# ETH_PCIE_PHY.net
KiCad netlist of a schematic drawn in Altium Designer
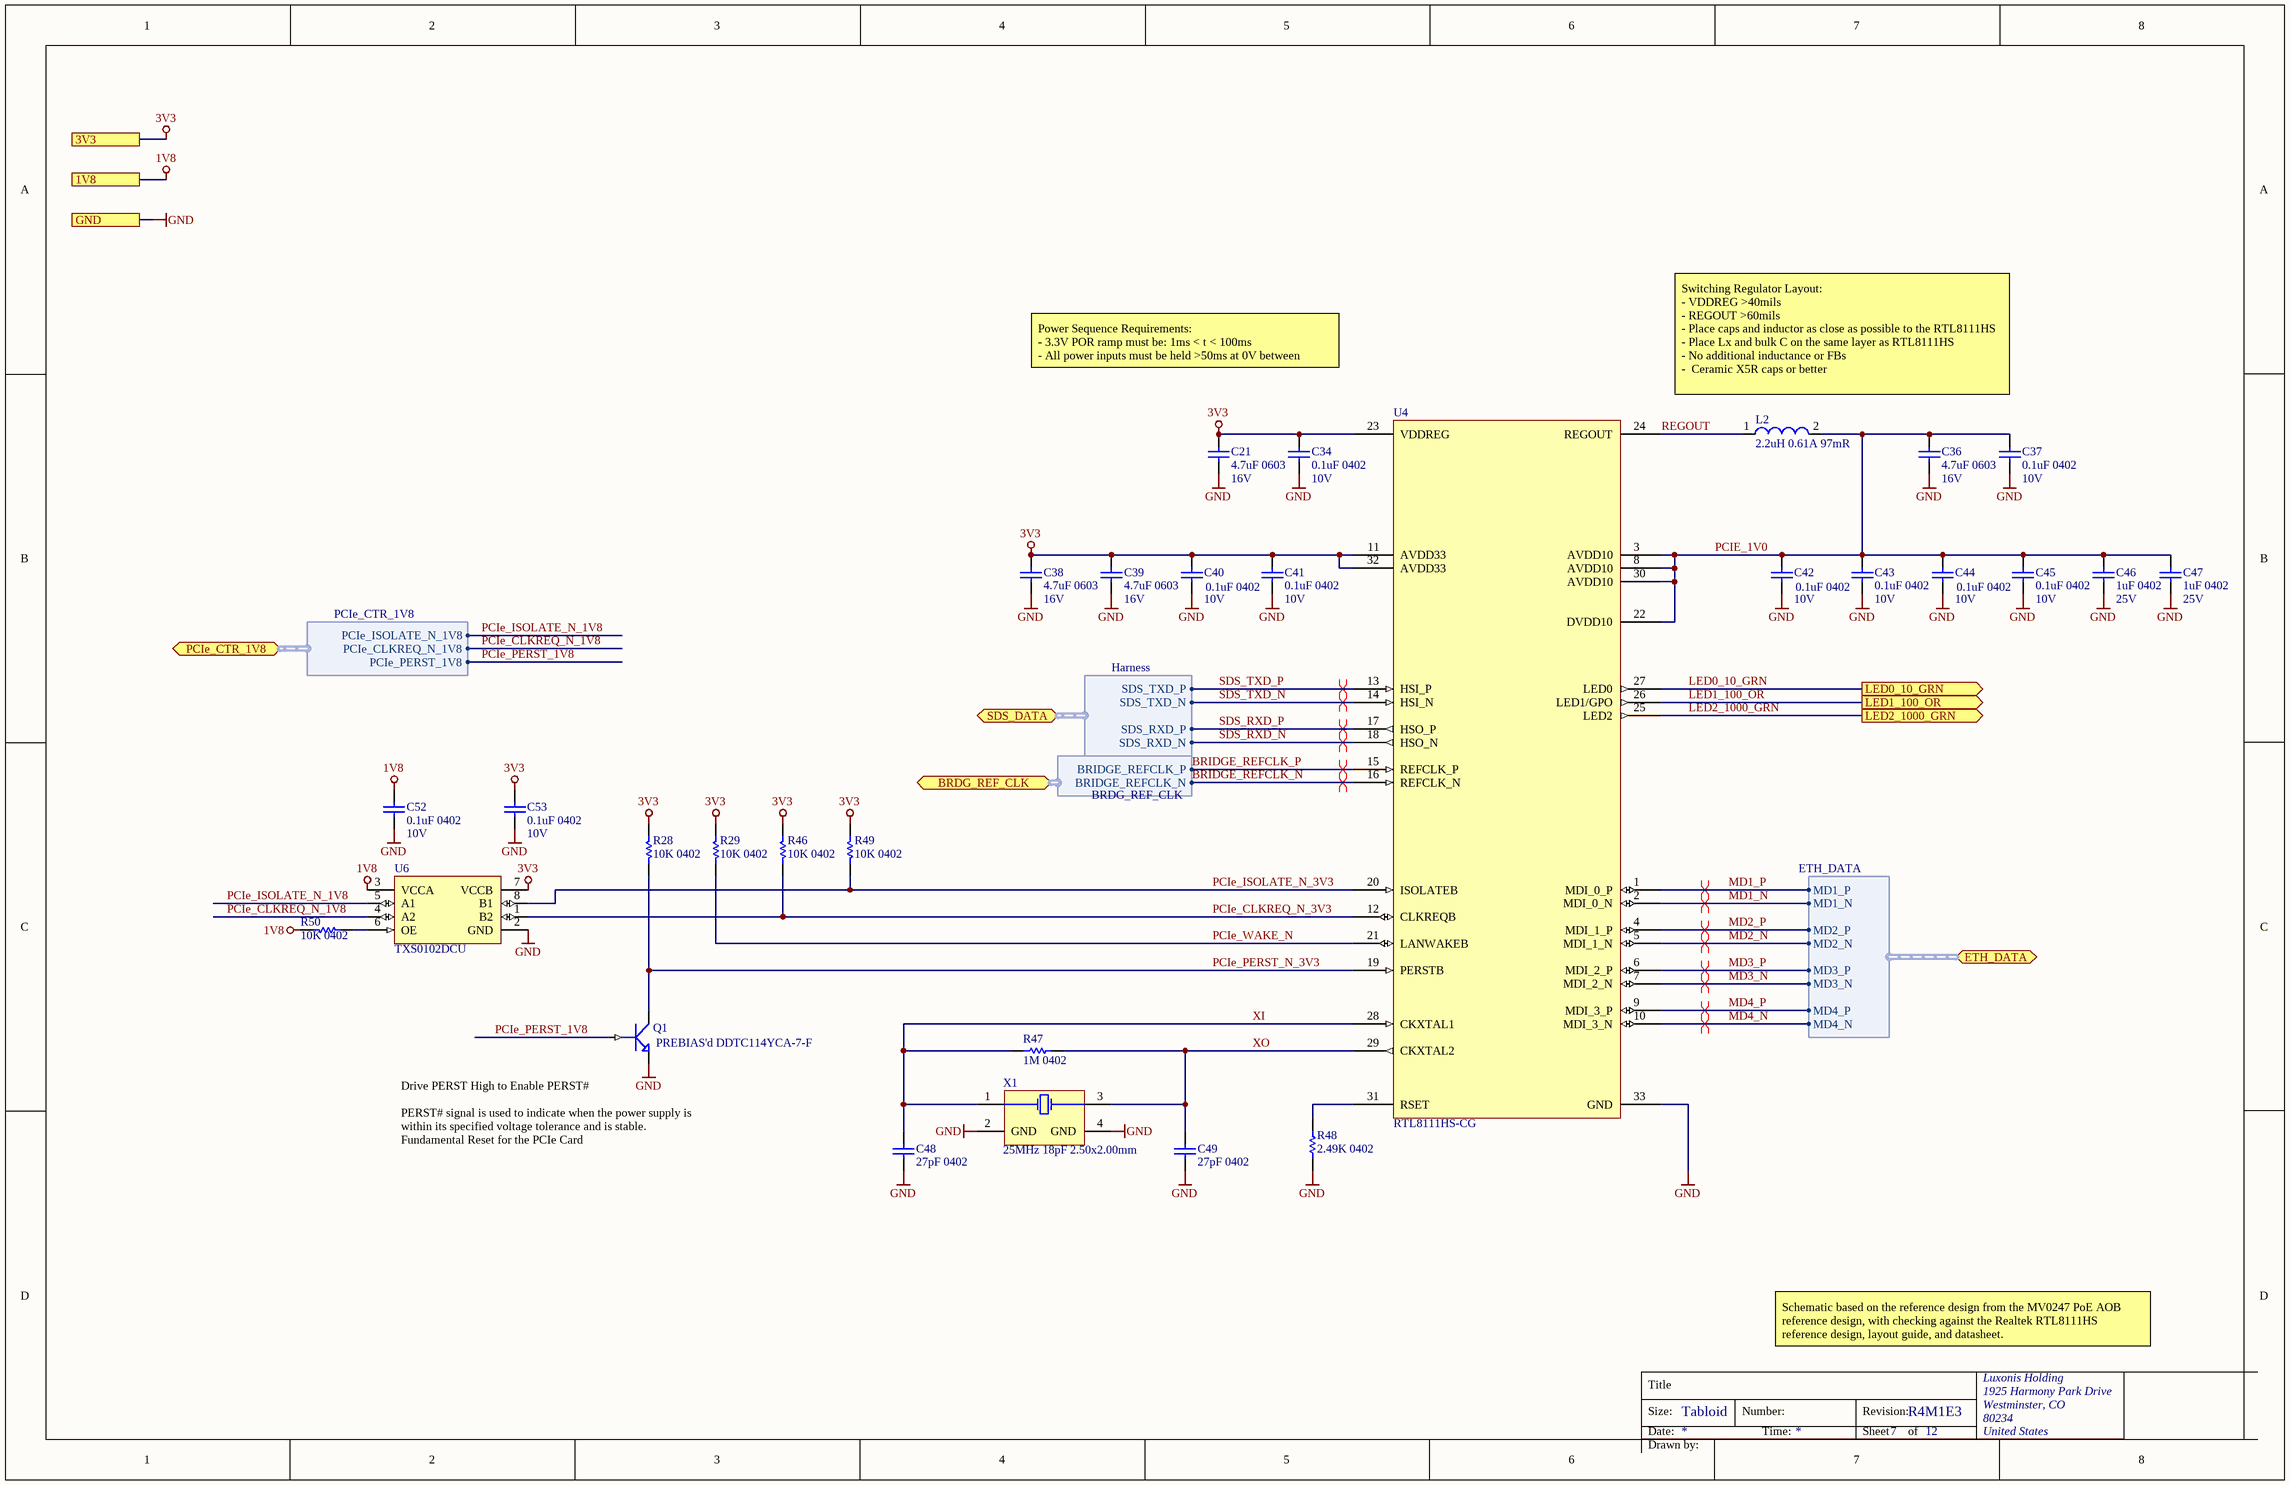
[diagram p0: ETH_PCIE_PHY.SchDoc]

(export (version "E")
  (design (tool "Eeschema 10.0.6"))
  (components
    (comp (ref "C21")
      (value "4.7uF 0603")
      (footprint "CAP_Altium_Vault_Generic:CAPC0603(1608)100_N")
      (description "CAP CER 4.7UF 16V X5R 0603 10%")
      (fields (field (name "TOLERANCE") "10%") (field (name "VOLTAGE RATING") "16V"))
      (libsource (lib "LuxonisMaster") (part "GRM188R61C475KAAJD"))
    )
    (comp (ref "C34")
      (value "0.1uF 0402")
      (footprint "CAP_Altium_Vault_Generic:CAPC0402(1005)70_N")
      (description "CAP CER 0.1UF 10V X7R 0402 5%")
      (fields (field (name "TOLERANCE") "5%") (field (name "VOLTAGE RATING") "10V"))
      (libsource (lib "LuxonisMaster") (part "GRM155R71A104JA01D"))
    )
    (comp (ref "C36")
      (value "4.7uF 0603")
      (footprint "CAP_Altium_Vault_Generic:CAPC0603(1608)100_N")
      (description "CAP CER 4.7UF 16V X5R 0603 10%")
      (fields (field (name "TOLERANCE") "10%") (field (name "VOLTAGE RATING") "16V"))
      (libsource (lib "LuxonisMaster") (part "GRM188R61C475KAAJD"))
    )
    (comp (ref "C37")
      (value "0.1uF 0402")
      (footprint "CAP_Altium_Vault_Generic:CAPC0402(1005)70_N")
      (description "CAP CER 0.1UF 10V X7R 0402 5%")
      (fields (field (name "TOLERANCE") "5%") (field (name "VOLTAGE RATING") "10V"))
      (libsource (lib "LuxonisMaster") (part "GRM155R71A104JA01D"))
    )
    (comp (ref "C38")
      (value "4.7uF 0603")
      (footprint "CAP_Altium_Vault_Generic:CAPC0603(1608)100_N")
      (description "CAP CER 4.7UF 16V X5R 0603 10%")
      (fields (field (name "TOLERANCE") "10%") (field (name "VOLTAGE RATING") "16V"))
      (libsource (lib "LuxonisMaster") (part "GRM188R61C475KAAJD"))
    )
    (comp (ref "C39")
      (value "4.7uF 0603")
      (footprint "CAP_Altium_Vault_Generic:CAPC0603(1608)100_N")
      (description "CAP CER 4.7UF 16V X5R 0603 10%")
      (fields (field (name "TOLERANCE") "10%") (field (name "VOLTAGE RATING") "16V"))
      (libsource (lib "LuxonisMaster") (part "GRM188R61C475KAAJD"))
    )
    (comp (ref "C40")
      (value "0.1uF 0402")
      (footprint "CAP_Altium_Vault_Generic:CAPC0402(1005)70_N")
      (description "CAP CER 0.1UF 10V X7R 0402 5%")
      (fields (field (name "TOLERANCE") "5%") (field (name "VOLTAGE RATING") "10V"))
      (libsource (lib "LuxonisMaster") (part "GRM155R71A104JA01D"))
    )
    (comp (ref "C41")
      (value "0.1uF 0402")
      (footprint "CAP_Altium_Vault_Generic:CAPC0402(1005)70_N")
      (description "CAP CER 0.1UF 10V X7R 0402 5%")
      (fields (field (name "TOLERANCE") "5%") (field (name "VOLTAGE RATING") "10V"))
      (libsource (lib "LuxonisMaster") (part "GRM155R71A104JA01D"))
    )
    (comp (ref "C42")
      (value "0.1uF 0402")
      (footprint "CAP_Altium_Vault_Generic:CAPC0402(1005)70_N")
      (description "CAP CER 0.1UF 10V X7R 0402 5%")
      (fields (field (name "TOLERANCE") "5%") (field (name "VOLTAGE RATING") "10V"))
      (libsource (lib "LuxonisMaster") (part "GRM155R71A104JA01D"))
    )
    (comp (ref "C43")
      (value "0.1uF 0402")
      (footprint "CAP_Altium_Vault_Generic:CAPC0402(1005)70_N")
      (description "CAP CER 0.1UF 10V X7R 0402 5%")
      (fields (field (name "TOLERANCE") "5%") (field (name "VOLTAGE RATING") "10V"))
      (libsource (lib "LuxonisMaster") (part "GRM155R71A104JA01D"))
    )
    (comp (ref "C44")
      (value "0.1uF 0402")
      (footprint "CAP_Altium_Vault_Generic:CAPC0402(1005)70_N")
      (description "CAP CER 0.1UF 10V X7R 0402 5%")
      (fields (field (name "TOLERANCE") "5%") (field (name "VOLTAGE RATING") "10V"))
      (libsource (lib "LuxonisMaster") (part "GRM155R71A104JA01D"))
    )
    (comp (ref "C45")
      (value "0.1uF 0402")
      (footprint "CAP_Altium_Vault_Generic:CAPC0402(1005)70_N")
      (description "CAP CER 0.1UF 10V X7R 0402 5%")
      (fields (field (name "TOLERANCE") "5%") (field (name "VOLTAGE RATING") "10V"))
      (libsource (lib "LuxonisMaster") (part "GRM155R71A104JA01D"))
    )
    (comp (ref "C46")
      (value "1uF 0402")
      (footprint "CAP_Altium_Vault_Generic:CAPC0402(1005)70_N")
      (description "CAP CER 1UF 25V X5R 0402 10%")
      (fields
        (field (name "TOLERANCE") "10%")
        (field (name "VOLTAGE") "25V")
        (field (name "VOLTAGE RATING") "25V")
      )
      (libsource (lib "LuxonisMaster") (part "GRM155R61E105KA12D"))
    )
    (comp (ref "C47")
      (value "1uF 0402")
      (footprint "CAP_Altium_Vault_Generic:CAPC0402(1005)70_N")
      (description "CAP CER 1UF 25V X5R 0402 10%")
      (fields
        (field (name "TOLERANCE") "10%")
        (field (name "VOLTAGE") "25V")
        (field (name "VOLTAGE RATING") "25V")
      )
      (libsource (lib "LuxonisMaster") (part "GRM155R61E105KA12D"))
    )
    (comp (ref "C48")
      (value "27pF 0402")
      (footprint "CAP_Altium_Vault_Generic:CAPC0402(1005)60_N")
      (description "CAP CER 27PF 50V C0G/NP0 0402")
      (fields (field (name "TOLERANCE") "5%") (field (name "VOLTAGE") "50V"))
      (libsource (lib "BW2098POE") (part "C0402C270J5GACTU"))
    )
    (comp (ref "C49")
      (value "27pF 0402")
      (footprint "CAP_Altium_Vault_Generic:CAPC0402(1005)60_N")
      (description "CAP CER 27PF 50V C0G/NP0 0402")
      (fields (field (name "TOLERANCE") "5%") (field (name "VOLTAGE") "50V"))
      (libsource (lib "BW2098POE") (part "C0402C270J5GACTU"))
    )
    (comp (ref "C52")
      (value "0.1uF 0402")
      (footprint "CAP_Altium_Vault_Generic:CAPC0402(1005)70_N")
      (description "CAP CER 0.1UF 10V X7R 0402 5%")
      (fields (field (name "TOLERANCE") "5%") (field (name "VOLTAGE RATING") "10V"))
      (libsource (lib "LuxonisMaster") (part "GRM155R71A104JA01D"))
    )
    (comp (ref "C53")
      (value "0.1uF 0402")
      (footprint "CAP_Altium_Vault_Generic:CAPC0402(1005)70_N")
      (description "CAP CER 0.1UF 10V X7R 0402 5%")
      (fields (field (name "TOLERANCE") "5%") (field (name "VOLTAGE RATING") "10V"))
      (libsource (lib "LuxonisMaster") (part "GRM155R71A104JA01D"))
    )
    (comp (ref "L2")
      (value "2.2uH 0.61A 97mR")
      (footprint "BW2098POE:LQH32NH2R2J23L")
      (description "FIXED IND 2.2UH 610MA 97MOHM SMD")
      (fields (field (name "TOLERANCE") "5%"))
      (libsource (lib "BW2098POE") (part "LQH32NH2R2J23L"))
    )
    (comp (ref "Q1")
      (value "PREBIAS'd DDTC114YCA-7-F")
      (footprint "BW2098POE:DDTC114YCA-7-F")
      (description "TRANS PREBIAS NPN 200MW SOT23-3")
      (libsource (lib "BW2098POE") (part "DDTC114YCA-7-F"))
    )
    (comp (ref "R28")
      (value "10K 0402")
      (footprint "RES_Altium_Vault_Generic:RESC0402(1005)_N")
      (fields (field (name "TOLERANCE") "1%"))
      (libsource (lib "LuxonisMaster") (part "RC0402FR-1310KL"))
    )
    (comp (ref "R29")
      (value "10K 0402")
      (footprint "RES_Altium_Vault_Generic:RESC0402(1005)_N")
      (fields (field (name "TOLERANCE") "1%"))
      (libsource (lib "LuxonisMaster") (part "RC0402FR-1310KL"))
    )
    (comp (ref "R46")
      (value "10K 0402")
      (footprint "RES_Altium_Vault_Generic:RESC0402(1005)_N")
      (fields (field (name "TOLERANCE") "1%"))
      (libsource (lib "LuxonisMaster") (part "RC0402FR-1310KL"))
    )
    (comp (ref "R47")
      (value "1M 0402")
      (footprint "RES_Altium_Vault_Generic:RESC0402(1005)_N")
      (description "RES SMD 1M OHM 1% 1/16W 0402")
      (fields (field (name "TOLERANCE") "1%"))
      (libsource (lib "LuxonisMaster") (part "RC0402FR-071ML"))
    )
    (comp (ref "R48")
      (value "2.49K 0402")
      (footprint "RES_Altium_Vault_Generic:RESC0402(1005)_N")
      (description "RES SMD 2.49K OHM 1% 1/16W 0402")
      (fields (field (name "TOLERANCE") "1%"))
      (libsource (lib "BW2098POE") (part "RC0402FR-072K49L"))
    )
    (comp (ref "R49")
      (value "10K 0402")
      (footprint "RES_Altium_Vault_Generic:RESC0402(1005)_N")
      (fields (field (name "TOLERANCE") "1%"))
      (libsource (lib "LuxonisMaster") (part "RC0402FR-1310KL"))
    )
    (comp (ref "R50")
      (value "10K 0402")
      (footprint "RES_Altium_Vault_Generic:RESC0402(1005)_N")
      (fields (field (name "TOLERANCE") "1%"))
      (libsource (lib "LuxonisMaster") (part "RC0402FR-1310KL"))
    )
    (comp (ref "U4")
      (value "RTL8111HS-CG")
      (footprint "BW2098POE:RTL8111Hx-CG")
      (description "IC ETHERNET/PCIe PHY Realtek")
      (libsource (lib "BW2098POE") (part "RTL8111HS"))
    )
    (comp (ref "U6")
      (value "TXS0102DCU")
      (footprint "BW2098POE:TXS0102DCUR")
      (description "TEXAS INSTRUMENTS - TXS0102DCUR - IC, TRANSLATOR, 2 BIT, BI, US-8")
      (libsource (lib "BW2098POE") (part "TXS0102DCUR"))
    )
    (comp (ref "X1")
      (value "25MHz 18pF 2.50x2.00mm")
      (footprint "BW2098POE:ECS-250-18-36B-CKY-TR")
      (description "CRYSTAL 25.0000MHZ 18PF SMD 25MHz ±10ppm Crystal 18pF 50 Ohms 4-SMD, No Lead")
      (libsource (lib "BW2098POE") (part "ECS-250-18-36B-CKY-TR"))
    )
  )
  (nets
    (net (code "5") (name "/BRIDGE_REFCLK_N") (class "Default")
      (node (ref "U4") (pin "16") (pinfunction "REFCLK_N_16") (pintype "input"))
    )
    (net (code "6") (name "/BRIDGE_REFCLK_P") (class "Default")
      (node (ref "U4") (pin "15") (pinfunction "REFCLK_P_15") (pintype "input"))
    )
    (net (code "7") (name "/LED0_10_GRN") (class "Default")
      (node (ref "U4") (pin "27") (pinfunction "LED0_27") (pintype "output"))
    )
    (net (code "8") (name "/LED1_100_OR") (class "Default")
      (node (ref "U4") (pin "26") (pinfunction "LED1/GPO_26") (pintype "output"))
    )
    (net (code "9") (name "/LED2_1000_GRN") (class "Default")
      (node (ref "U4") (pin "25") (pinfunction "LED2_25") (pintype "output"))
    )
    (net (code "10") (name "/MD1_N") (class "Default")
      (node (ref "U4") (pin "2") (pinfunction "MDI_0_N_2") (pintype "bidirectional"))
    )
    (net (code "11") (name "/MD1_P") (class "Default")
      (node (ref "U4") (pin "1") (pinfunction "MDI_0_P_1") (pintype "bidirectional"))
    )
    (net (code "12") (name "/MD2_N") (class "Default")
      (node (ref "U4") (pin "5") (pinfunction "MDI_1_N_5") (pintype "bidirectional"))
    )
    (net (code "13") (name "/MD2_P") (class "Default")
      (node (ref "U4") (pin "4") (pinfunction "MDI_1_P_4") (pintype "bidirectional"))
    )
    (net (code "14") (name "/MD3_N") (class "Default")
      (node (ref "U4") (pin "7") (pinfunction "MDI_2_N_7") (pintype "bidirectional"))
    )
    (net (code "15") (name "/MD3_P") (class "Default")
      (node (ref "U4") (pin "6") (pinfunction "MDI_2_P_6") (pintype "bidirectional"))
    )
    (net (code "16") (name "/MD4_N") (class "Default")
      (node (ref "U4") (pin "10") (pinfunction "MDI_3_N_10") (pintype "bidirectional"))
    )
    (net (code "17") (name "/MD4_P") (class "Default")
      (node (ref "U4") (pin "9") (pinfunction "MDI_3_P_9") (pintype "bidirectional"))
    )
    (net (code "18") (name "/PCIE_1V0") (class "Default")
      (node (ref "C36") (pin "2") (pinfunction "2_2") (pintype "passive"))
      (node (ref "C37") (pin "2") (pinfunction "2_2") (pintype "passive"))
      (node (ref "C42") (pin "2") (pinfunction "2_2") (pintype "passive"))
      (node (ref "C43") (pin "2") (pinfunction "2_2") (pintype "passive"))
      (node (ref "C44") (pin "2") (pinfunction "2_2") (pintype "passive"))
      (node (ref "C45") (pin "2") (pinfunction "2_2") (pintype "passive"))
      (node (ref "C46") (pin "2") (pinfunction "2_2") (pintype "passive"))
      (node (ref "C47") (pin "2") (pinfunction "2_2") (pintype "passive"))
      (node (ref "L2") (pin "2") (pinfunction "2_2") (pintype "passive"))
      (node (ref "U4") (pin "22") (pinfunction "DVDD10_22") (pintype "passive"))
      (node (ref "U4") (pin "3") (pinfunction "AVDD10_3") (pintype "passive"))
      (node (ref "U4") (pin "30") (pinfunction "AVDD10_30") (pintype "passive"))
      (node (ref "U4") (pin "8") (pinfunction "AVDD10_8") (pintype "passive"))
    )
    (net (code "19") (name "/PCIe_CLKREQ_N_1V8") (class "Default")
      (node (ref "U6") (pin "4") (pinfunction "A2_4") (pintype "bidirectional"))
    )
    (net (code "20") (name "/PCIe_CLKREQ_N_3V3") (class "Default")
      (node (ref "R46") (pin "2") (pinfunction "2_2") (pintype "passive"))
      (node (ref "U4") (pin "12") (pinfunction "CLKREQB_12") (pintype "bidirectional"))
      (node (ref "U6") (pin "1") (pinfunction "B2_1") (pintype "bidirectional"))
    )
    (net (code "21") (name "/PCIe_ISOLATE_N_1V8") (class "Default")
      (node (ref "U6") (pin "5") (pinfunction "A1_5") (pintype "bidirectional"))
    )
    (net (code "22") (name "/PCIe_ISOLATE_N_3V3") (class "Default")
      (node (ref "R49") (pin "2") (pinfunction "2_2") (pintype "passive"))
      (node (ref "U4") (pin "20") (pinfunction "ISOLATEB_20") (pintype "input"))
      (node (ref "U6") (pin "8") (pinfunction "B1_8") (pintype "bidirectional"))
    )
    (net (code "23") (name "/PCIe_PERST_1V8") (class "Default")
      (node (ref "Q1") (pin "1") (pinfunction "B_1") (pintype "input"))
    )
    (net (code "24") (name "/PCIe_PERST_N_3V3") (class "Default")
      (node (ref "Q1") (pin "3") (pinfunction "C_3") (pintype "passive"))
      (node (ref "R28") (pin "2") (pinfunction "2_2") (pintype "passive"))
      (node (ref "U4") (pin "19") (pinfunction "PERSTB_19") (pintype "input"))
    )
    (net (code "25") (name "/PCIe_WAKE_N") (class "Default")
      (node (ref "R29") (pin "2") (pinfunction "2_2") (pintype "passive"))
      (node (ref "U4") (pin "21") (pinfunction "LANWAKEB_21") (pintype "bidirectional"))
    )
    (net (code "26") (name "/REGOUT") (class "Default")
      (node (ref "L2") (pin "1") (pinfunction "1_1") (pintype "passive"))
      (node (ref "U4") (pin "24") (pinfunction "REGOUT_24") (pintype "passive"))
    )
    (net (code "27") (name "/SDS_RXD_N") (class "Default")
      (node (ref "U4") (pin "18") (pinfunction "HSO_N_18") (pintype "output"))
    )
    (net (code "28") (name "/SDS_RXD_P") (class "Default")
      (node (ref "U4") (pin "17") (pinfunction "HSO_P_17") (pintype "output"))
    )
    (net (code "29") (name "/SDS_TXD_N") (class "Default")
      (node (ref "U4") (pin "14") (pinfunction "HSI_N_14") (pintype "input"))
    )
    (net (code "30") (name "/SDS_TXD_P") (class "Default")
      (node (ref "U4") (pin "13") (pinfunction "HSI_P_13") (pintype "input"))
    )
    (net (code "31") (name "/XI") (class "Default")
      (node (ref "C48") (pin "2") (pinfunction "2_2") (pintype "passive"))
      (node (ref "R47") (pin "1") (pinfunction "1_1") (pintype "passive"))
      (node (ref "U4") (pin "28") (pinfunction "CKXTAL1_28") (pintype "input"))
      (node (ref "X1") (pin "1") (pinfunction "X1_1") (pintype "passive"))
    )
    (net (code "32") (name "/XO") (class "Default")
      (node (ref "C49") (pin "2") (pinfunction "2_2") (pintype "passive"))
      (node (ref "R47") (pin "2") (pinfunction "2_2") (pintype "passive"))
      (node (ref "U4") (pin "29") (pinfunction "CKXTAL2_29") (pintype "output"))
      (node (ref "X1") (pin "3") (pinfunction "X2_3") (pintype "passive"))
    )
    (net (code "37") (name "1V8") (class "Default")
      (node (ref "C52") (pin "2") (pinfunction "2_2") (pintype "passive"))
      (node (ref "R50") (pin "2") (pinfunction "2_2") (pintype "passive"))
      (node (ref "U6") (pin "3") (pinfunction "VCCA_3") (pintype "power_in"))
    )
    (net (code "38") (name "3V3") (class "Default")
      (node (ref "C21") (pin "2") (pinfunction "2_2") (pintype "passive"))
      (node (ref "C34") (pin "2") (pinfunction "2_2") (pintype "passive"))
      (node (ref "C38") (pin "2") (pinfunction "2_2") (pintype "passive"))
      (node (ref "C39") (pin "2") (pinfunction "2_2") (pintype "passive"))
      (node (ref "C40") (pin "2") (pinfunction "2_2") (pintype "passive"))
      (node (ref "C41") (pin "2") (pinfunction "2_2") (pintype "passive"))
      (node (ref "C53") (pin "2") (pinfunction "2_2") (pintype "passive"))
      (node (ref "R28") (pin "1") (pinfunction "1_1") (pintype "passive"))
      (node (ref "R29") (pin "1") (pinfunction "1_1") (pintype "passive"))
      (node (ref "R46") (pin "1") (pinfunction "1_1") (pintype "passive"))
      (node (ref "R49") (pin "1") (pinfunction "1_1") (pintype "passive"))
      (node (ref "U4") (pin "11") (pinfunction "AVDD33_11") (pintype "passive"))
      (node (ref "U4") (pin "23") (pinfunction "VDDREG_23") (pintype "passive"))
      (node (ref "U4") (pin "32") (pinfunction "AVDD33_32") (pintype "passive"))
      (node (ref "U6") (pin "7") (pinfunction "VCCB_7") (pintype "power_in"))
    )
    (net (code "39") (name "GND") (class "Default")
      (node (ref "C21") (pin "1") (pinfunction "1_1") (pintype "passive"))
      (node (ref "C34") (pin "1") (pinfunction "1_1") (pintype "passive"))
      (node (ref "C36") (pin "1") (pinfunction "1_1") (pintype "passive"))
      (node (ref "C37") (pin "1") (pinfunction "1_1") (pintype "passive"))
      (node (ref "C38") (pin "1") (pinfunction "1_1") (pintype "passive"))
      (node (ref "C39") (pin "1") (pinfunction "1_1") (pintype "passive"))
      (node (ref "C40") (pin "1") (pinfunction "1_1") (pintype "passive"))
      (node (ref "C41") (pin "1") (pinfunction "1_1") (pintype "passive"))
      (node (ref "C42") (pin "1") (pinfunction "1_1") (pintype "passive"))
      (node (ref "C43") (pin "1") (pinfunction "1_1") (pintype "passive"))
      (node (ref "C44") (pin "1") (pinfunction "1_1") (pintype "passive"))
      (node (ref "C45") (pin "1") (pinfunction "1_1") (pintype "passive"))
      (node (ref "C46") (pin "1") (pinfunction "1_1") (pintype "passive"))
      (node (ref "C47") (pin "1") (pinfunction "1_1") (pintype "passive"))
      (node (ref "C48") (pin "1") (pinfunction "1_1") (pintype "passive"))
      (node (ref "C49") (pin "1") (pinfunction "1_1") (pintype "passive"))
      (node (ref "C52") (pin "1") (pinfunction "1_1") (pintype "passive"))
      (node (ref "C53") (pin "1") (pinfunction "1_1") (pintype "passive"))
      (node (ref "Q1") (pin "2") (pinfunction "E_2") (pintype "passive"))
      (node (ref "R48") (pin "1") (pinfunction "1_1") (pintype "passive"))
      (node (ref "U4") (pin "33") (pinfunction "GND_33") (pintype "passive"))
      (node (ref "U6") (pin "2") (pinfunction "GND_2") (pintype "power_in"))
      (node (ref "X1") (pin "2") (pinfunction "GND_2") (pintype "power_in"))
      (node (ref "X1") (pin "4") (pinfunction "GND_4") (pintype "power_in"))
    )
    (net (code "40") (name "Net-(U4-RSET)") (class "Default")
      (node (ref "R48") (pin "2") (pinfunction "2_2") (pintype "passive"))
      (node (ref "U4") (pin "31") (pinfunction "RSET_31") (pintype "passive"))
    )
    (net (code "41") (name "Net-(U6-OE)") (class "Default")
      (node (ref "R50") (pin "1") (pinfunction "1_1") (pintype "passive"))
      (node (ref "U6") (pin "6") (pinfunction "OE_6") (pintype "input"))
    )
  )
)
